# AmbaSat-1_version_2_0.net
KiCad netlist of a schematic drawn in EAGLE
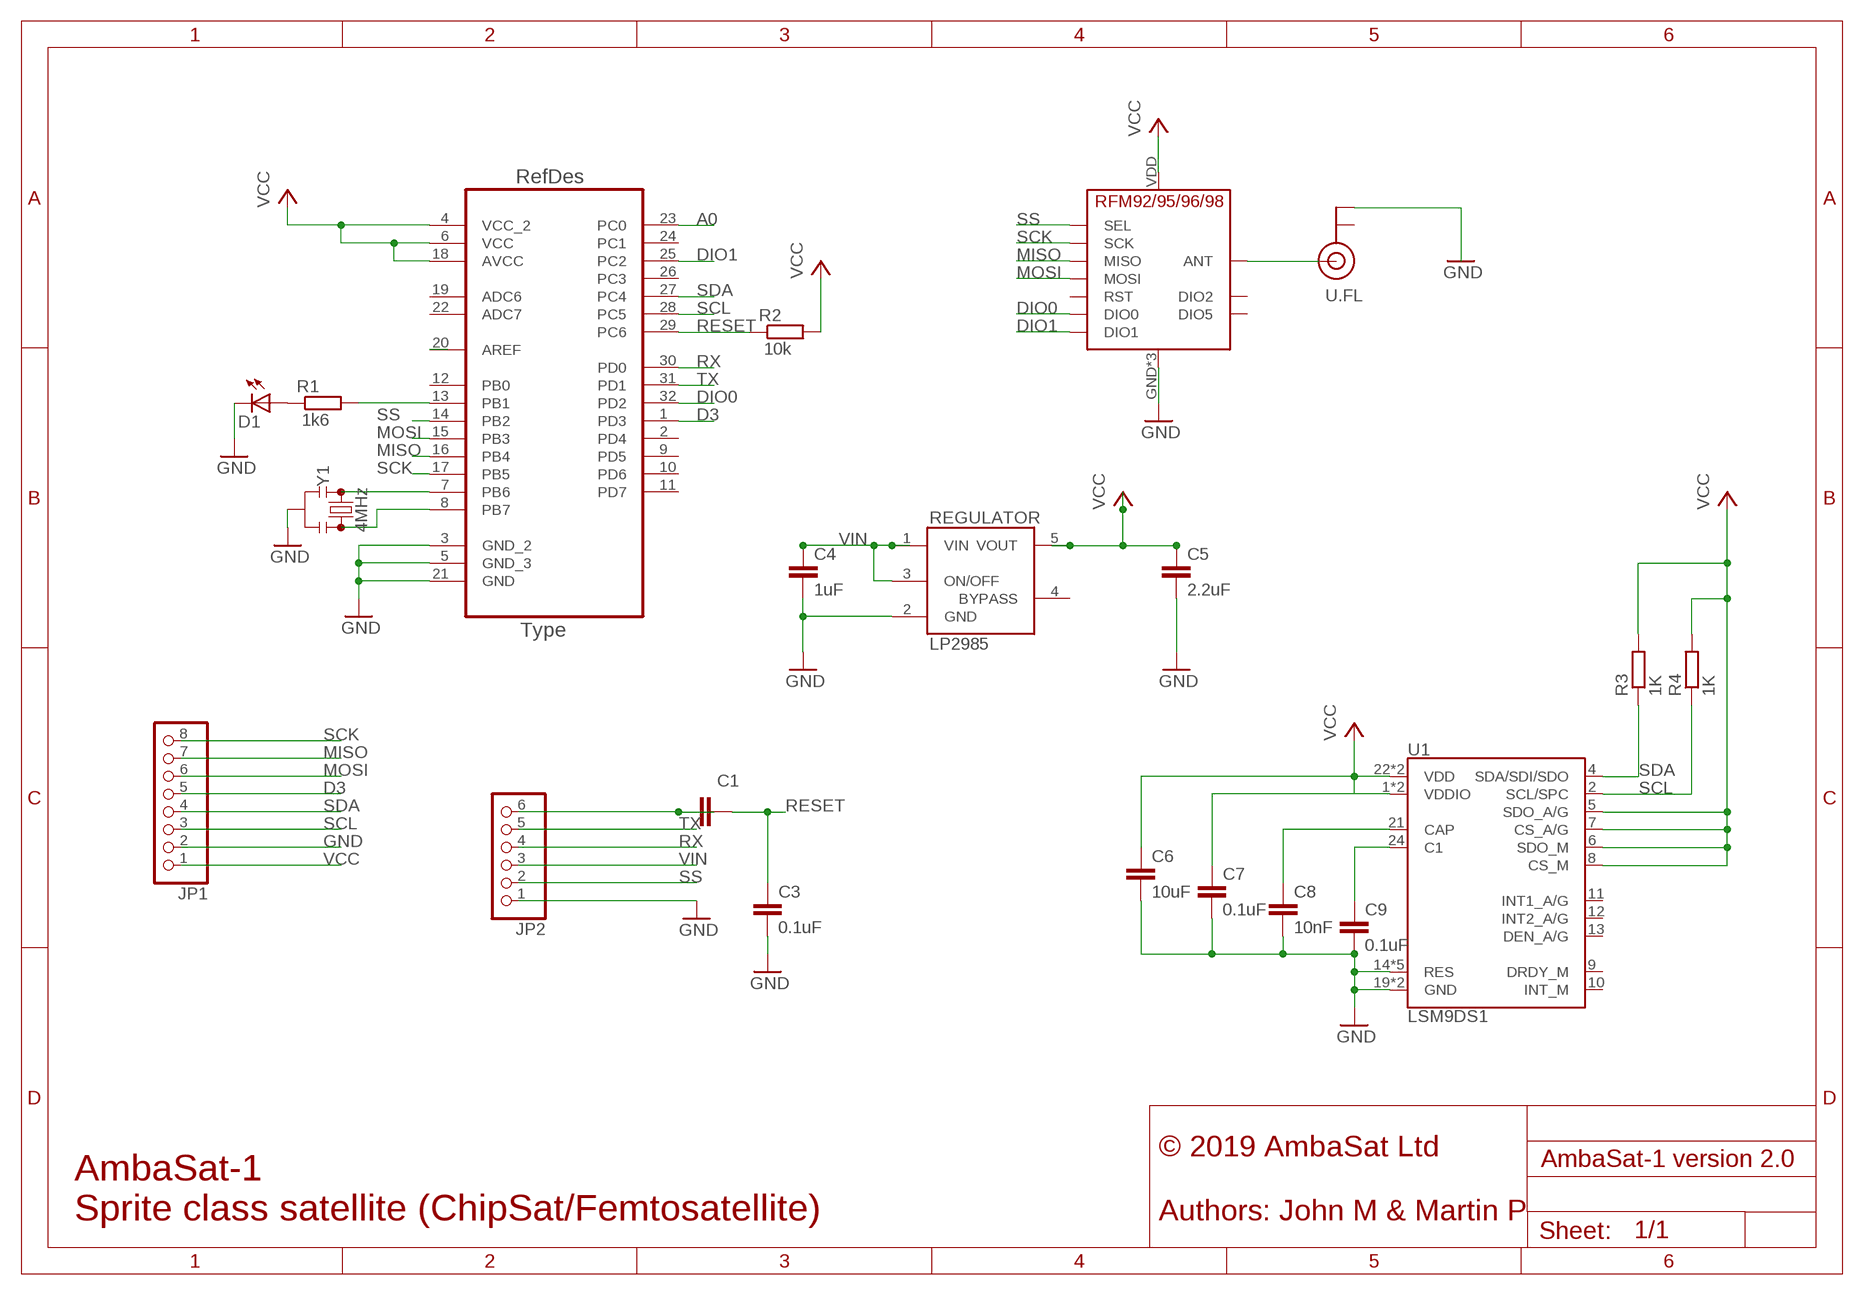
[diagram p0: schematic, sheet 1]

(export (version "E")
  (design (tool "Eeschema 10.0.6"))
  (components
    (comp (ref "ATMEGA328P-AU")
      (value "ATMEGA328P-AU")
      (footprint "eagle-import:QFP80P900X900X120-32N")
      (libsource (lib "eagle-import") (part "ATMEGA328P-AU"))
    )
    (comp (ref "C1")
      (value "1uF")
      (footprint "eagle-import:C0805K")
      (libsource (lib "eagle-import") (part "C-EUC0805K"))
    )
    (comp (ref "C3")
      (value "0.1uF")
      (footprint "eagle-import:C0805K")
      (libsource (lib "eagle-import") (part "C-EUC0805K"))
    )
    (comp (ref "C4")
      (value "1uF")
      (footprint "eagle-import:C0805K")
      (libsource (lib "eagle-import") (part "C-EUC0805K"))
    )
    (comp (ref "C5")
      (value "2.2uF")
      (footprint "eagle-import:C0805K")
      (libsource (lib "eagle-import") (part "C-EUC0805K"))
    )
    (comp (ref "C6")
      (value "10uF")
      (footprint "eagle-import:C0805K")
      (libsource (lib "eagle-import") (part "C-EUC0805K"))
    )
    (comp (ref "C7")
      (value "0.1uF")
      (footprint "eagle-import:C0805K")
      (libsource (lib "eagle-import") (part "C-EUC0805K"))
    )
    (comp (ref "C8")
      (value "10nF")
      (footprint "eagle-import:C0805K")
      (libsource (lib "eagle-import") (part "C-EUC0805K"))
    )
    (comp (ref "C9")
      (value "0.1uF")
      (footprint "eagle-import:C0805K")
      (libsource (lib "eagle-import") (part "C-EUC0805K"))
    )
    (comp (ref "D1")
      (value "LEDCHIP-LED0805")
      (footprint "eagle-import:CHIP-LED0805")
      (libsource (lib "eagle-import") (part "LEDCHIP-LED0805"))
    )
    (comp (ref "JP1")
      (value "PINHD-1X8")
      (footprint "eagle-import:1X08")
      (libsource (lib "eagle-import") (part "PINHD-1X8"))
    )
    (comp (ref "JP2")
      (value "PINHD-1X6")
      (footprint "eagle-import:1X06")
      (libsource (lib "eagle-import") (part "PINHD-1X6"))
    )
    (comp (ref "R1")
      (value "1k6")
      (footprint "eagle-import:M0805")
      (libsource (lib "eagle-import") (part "R-EU_M0805"))
    )
    (comp (ref "R2")
      (value "10k")
      (footprint "eagle-import:M0805")
      (libsource (lib "eagle-import") (part "R-EU_M0805"))
    )
    (comp (ref "R3")
      (value "1K")
      (footprint "eagle-import:M0805")
      (libsource (lib "eagle-import") (part "R-EU_M0805"))
    )
    (comp (ref "R4")
      (value "1K")
      (footprint "eagle-import:M0805")
      (libsource (lib "eagle-import") (part "R-EU_M0805"))
    )
    (comp (ref "REGULATOR")
      (value "LP2985AIM5-3.3")
      (footprint "eagle-import:SOT25")
      (libsource (lib "eagle-import") (part "LP2985AIM5-3.3"))
    )
    (comp (ref "RFM95")
      (value "RFM95")
      (footprint "eagle-import:RFM95")
      (libsource (lib "eagle-import") (part "RFM95"))
    )
    (comp (ref "U.FL")
      (value "U.FL")
      (footprint "eagle-import:U.FL")
      (libsource (lib "eagle-import") (part "U.FL"))
    )
    (comp (ref "U1")
      (value "LSM9DS1")
      (footprint "eagle-import:LGA24-8X4")
      (libsource (lib "eagle-import") (part "LSM9DS1"))
    )
    (comp (ref "Y1")
      (value "4MHz")
      (footprint "eagle-import:RESONATOR-SMD-4.5X2.0")
      (libsource (lib "eagle-import") (part "RESONATOR-4MHZSMD-4.5X2"))
    )
  )
  (nets
    (net (code "1") (name "/A0") (class "Default")
      (node (ref "ATMEGA328P-AU") (pin "23") (pinfunction "PC0_23") (pintype "bidirectional"))
    )
    (net (code "2") (name "/BYPASS") (class "Default")
      (node (ref "REGULATOR") (pin "4") (pinfunction "BYPASS_4") (pintype "power_in"))
    )
    (net (code "3") (name "/D3") (class "Default")
      (node (ref "ATMEGA328P-AU") (pin "1") (pinfunction "PD3_1") (pintype "bidirectional"))
      (node (ref "JP1") (pin "5") (pinfunction "5_5") (pintype "passive"))
    )
    (net (code "4") (name "/DIO0") (class "Default")
      (node (ref "ATMEGA328P-AU") (pin "32") (pinfunction "PD2_32") (pintype "bidirectional"))
      (node (ref "RFM95") (pin "DIO0") (pinfunction "DIO0_DIO0") (pintype "open_collector"))
    )
    (net (code "5") (name "/DIO1") (class "Default")
      (node (ref "ATMEGA328P-AU") (pin "25") (pinfunction "PC2_25") (pintype "bidirectional"))
      (node (ref "RFM95") (pin "DIO1") (pinfunction "DIO1_DIO1") (pintype "open_collector"))
    )
    (net (code "6") (name "/MISO") (class "Default")
      (node (ref "ATMEGA328P-AU") (pin "16") (pinfunction "PB4_16") (pintype "bidirectional"))
      (node (ref "JP1") (pin "7") (pinfunction "7_7") (pintype "passive"))
      (node (ref "RFM95") (pin "MISO") (pinfunction "MISO_MISO") (pintype "input"))
    )
    (net (code "7") (name "/MOSI") (class "Default")
      (node (ref "ATMEGA328P-AU") (pin "15") (pinfunction "PB3_15") (pintype "bidirectional"))
      (node (ref "JP1") (pin "6") (pinfunction "6_6") (pintype "passive"))
      (node (ref "RFM95") (pin "MOSI") (pinfunction "MOSI_MOSI") (pintype "output"))
    )
    (net (code "8") (name "/RESET") (class "Default")
      (node (ref "ATMEGA328P-AU") (pin "29") (pinfunction "PC6_29") (pintype "bidirectional"))
      (node (ref "C1") (pin "1") (pinfunction "1_1") (pintype "passive"))
      (node (ref "C3") (pin "1") (pinfunction "1_1") (pintype "passive"))
      (node (ref "R2") (pin "1") (pinfunction "1_1") (pintype "passive"))
    )
    (net (code "9") (name "/RX") (class "Default")
      (node (ref "ATMEGA328P-AU") (pin "30") (pinfunction "PD0_30") (pintype "bidirectional"))
      (node (ref "JP2") (pin "4") (pinfunction "4_4") (pintype "passive"))
    )
    (net (code "10") (name "/SCK") (class "Default")
      (node (ref "ATMEGA328P-AU") (pin "17") (pinfunction "PB5_17") (pintype "bidirectional"))
      (node (ref "JP1") (pin "8") (pinfunction "8_8") (pintype "passive"))
      (node (ref "RFM95") (pin "SCK") (pinfunction "SCK_SCK") (pintype "input"))
    )
    (net (code "11") (name "/SCL") (class "Default")
      (node (ref "ATMEGA328P-AU") (pin "28") (pinfunction "PC5_28") (pintype "bidirectional"))
      (node (ref "JP1") (pin "3") (pinfunction "3_3") (pintype "passive"))
      (node (ref "R4") (pin "1") (pinfunction "1_1") (pintype "passive"))
      (node (ref "U1") (pin "2") (pinfunction "SCL/SPC_2") (pintype "bidirectional"))
    )
    (net (code "12") (name "/SDA") (class "Default")
      (node (ref "ATMEGA328P-AU") (pin "27") (pinfunction "PC4_27") (pintype "bidirectional"))
      (node (ref "JP1") (pin "4") (pinfunction "4_4") (pintype "passive"))
      (node (ref "R3") (pin "1") (pinfunction "1_1") (pintype "passive"))
      (node (ref "U1") (pin "4") (pinfunction "SDA/SDI/SDO_4") (pintype "bidirectional"))
    )
    (net (code "13") (name "/SS") (class "Default")
      (node (ref "ATMEGA328P-AU") (pin "14") (pinfunction "PB2_14") (pintype "bidirectional"))
      (node (ref "JP2") (pin "2") (pinfunction "2_2") (pintype "passive"))
      (node (ref "RFM95") (pin "NSS") (pinfunction "SEL_NSS") (pintype "input"))
    )
    (net (code "14") (name "/TX") (class "Default")
      (node (ref "ATMEGA328P-AU") (pin "31") (pinfunction "PD1_31") (pintype "bidirectional"))
      (node (ref "JP2") (pin "5") (pinfunction "5_5") (pintype "passive"))
    )
    (net (code "15") (name "/VIN") (class "Default")
      (node (ref "C4") (pin "1") (pinfunction "1_1") (pintype "passive"))
      (node (ref "JP2") (pin "3") (pinfunction "3_3") (pintype "passive"))
      (node (ref "REGULATOR") (pin "1") (pinfunction "VIN_1") (pintype "power_in"))
      (node (ref "REGULATOR") (pin "3") (pinfunction "ON/OFF_3") (pintype "input"))
    )
    (net (code "16") (name "GND") (class "Default")
      (node (ref "ATMEGA328P-AU") (pin "21") (pinfunction "GND_21") (pintype "passive"))
      (node (ref "ATMEGA328P-AU") (pin "3") (pinfunction "GND_2_3") (pintype "passive"))
      (node (ref "ATMEGA328P-AU") (pin "5") (pinfunction "GND_3_5") (pintype "passive"))
      (node (ref "C3") (pin "2") (pinfunction "2_2") (pintype "passive"))
      (node (ref "C4") (pin "2") (pinfunction "2_2") (pintype "passive"))
      (node (ref "C5") (pin "2") (pinfunction "2_2") (pintype "passive"))
      (node (ref "C6") (pin "2") (pinfunction "2_2") (pintype "passive"))
      (node (ref "C7") (pin "2") (pinfunction "2_2") (pintype "passive"))
      (node (ref "C8") (pin "2") (pinfunction "2_2") (pintype "passive"))
      (node (ref "C9") (pin "2") (pinfunction "2_2") (pintype "passive"))
      (node (ref "D1") (pin "C") (pinfunction "C_C") (pintype "passive"))
      (node (ref "JP1") (pin "2") (pinfunction "2_2") (pintype "passive"))
      (node (ref "JP2") (pin "1") (pinfunction "1_1") (pintype "passive"))
      (node (ref "REGULATOR") (pin "2") (pinfunction "GND_2") (pintype "power_in"))
      (node (ref "RFM95") (pin "GND") (pinfunction "GND_GND") (pintype "power_in"))
      (node (ref "RFM95") (pin "GND1") (pinfunction "GND_GND1") (pintype "power_in"))
      (node (ref "RFM95") (pin "GND2") (pinfunction "GND_GND2") (pintype "power_in"))
      (node (ref "U1") (pin "14") (pinfunction "RES_14") (pintype "bidirectional"))
      (node (ref "U1") (pin "15") (pinfunction "RES_15") (pintype "bidirectional"))
      (node (ref "U1") (pin "16") (pinfunction "RES_16") (pintype "bidirectional"))
      (node (ref "U1") (pin "17") (pinfunction "RES_17") (pintype "bidirectional"))
      (node (ref "U1") (pin "18") (pinfunction "RES_18") (pintype "bidirectional"))
      (node (ref "U1") (pin "19") (pinfunction "GND_19") (pintype "bidirectional"))
      (node (ref "U1") (pin "20") (pinfunction "GND_20") (pintype "bidirectional"))
      (node (ref "Y1") (pin "2") (pinfunction "2_2") (pintype "passive"))
    )
    (net (code "17") (name "Net-(ATMEGA328P-AU-PB1)") (class "Default")
      (node (ref "ATMEGA328P-AU") (pin "13") (pinfunction "PB1_13") (pintype "bidirectional"))
      (node (ref "R1") (pin "2") (pinfunction "2_2") (pintype "passive"))
    )
    (net (code "18") (name "Net-(ATMEGA328P-AU-PB6)") (class "Default")
      (node (ref "ATMEGA328P-AU") (pin "7") (pinfunction "PB6_7") (pintype "bidirectional"))
      (node (ref "Y1") (pin "1") (pinfunction "1_1") (pintype "passive"))
    )
    (net (code "19") (name "Net-(ATMEGA328P-AU-PB7)") (class "Default")
      (node (ref "ATMEGA328P-AU") (pin "8") (pinfunction "PB7_8") (pintype "bidirectional"))
      (node (ref "Y1") (pin "3") (pinfunction "3_3") (pintype "passive"))
    )
    (net (code "20") (name "Net-(C1-Pad2)") (class "Default")
      (node (ref "C1") (pin "2") (pinfunction "2_2") (pintype "passive"))
      (node (ref "JP2") (pin "6") (pinfunction "6_6") (pintype "passive"))
    )
    (net (code "21") (name "Net-(D1-PadA)") (class "Default")
      (node (ref "D1") (pin "A") (pinfunction "A_A") (pintype "passive"))
      (node (ref "R1") (pin "1") (pinfunction "1_1") (pintype "passive"))
    )
    (net (code "22") (name "Net-(U1-C1)") (class "Default")
      (node (ref "C9") (pin "1") (pinfunction "1_1") (pintype "passive"))
      (node (ref "U1") (pin "24") (pinfunction "C1_24") (pintype "bidirectional"))
    )
    (net (code "23") (name "Net-(U1-CAP)") (class "Default")
      (node (ref "C8") (pin "1") (pinfunction "1_1") (pintype "passive"))
      (node (ref "U1") (pin "21") (pinfunction "CAP_21") (pintype "bidirectional"))
    )
    (net (code "24") (name "VCC") (class "Default")
      (node (ref "ATMEGA328P-AU") (pin "18") (pinfunction "AVCC_18") (pintype "power_in"))
      (node (ref "ATMEGA328P-AU") (pin "4") (pinfunction "VCC_2_4") (pintype "power_in"))
      (node (ref "ATMEGA328P-AU") (pin "6") (pinfunction "VCC_6") (pintype "power_in"))
      (node (ref "C5") (pin "1") (pinfunction "1_1") (pintype "passive"))
      (node (ref "C6") (pin "1") (pinfunction "1_1") (pintype "passive"))
      (node (ref "C7") (pin "1") (pinfunction "1_1") (pintype "passive"))
      (node (ref "JP1") (pin "1") (pinfunction "1_1") (pintype "passive"))
      (node (ref "R2") (pin "2") (pinfunction "2_2") (pintype "passive"))
      (node (ref "R3") (pin "2") (pinfunction "2_2") (pintype "passive"))
      (node (ref "R4") (pin "2") (pinfunction "2_2") (pintype "passive"))
      (node (ref "REGULATOR") (pin "5") (pinfunction "VOUT_5") (pintype "power_in"))
      (node (ref "RFM95") (pin "VDD") (pinfunction "VCC_VDD") (pintype "power_in"))
      (node (ref "U1") (pin "1") (pinfunction "VDDIO_1") (pintype "bidirectional"))
      (node (ref "U1") (pin "22") (pinfunction "VDD_22") (pintype "bidirectional"))
      (node (ref "U1") (pin "23") (pinfunction "VDD_23") (pintype "bidirectional"))
      (node (ref "U1") (pin "3") (pinfunction "VDDIO_3") (pintype "bidirectional"))
      (node (ref "U1") (pin "5") (pinfunction "SDO_A/G_5") (pintype "bidirectional"))
      (node (ref "U1") (pin "6") (pinfunction "SDO_M_6") (pintype "bidirectional"))
      (node (ref "U1") (pin "7") (pinfunction "CS_A/G_7") (pintype "bidirectional"))
      (node (ref "U1") (pin "8") (pinfunction "CS_M_8") (pintype "bidirectional"))
    )
    (net (code "25") (name "unconnected-(ATMEGA328P-AU-ADC6-Pad19)") (class "Default")
      (node (ref "ATMEGA328P-AU") (pin "19") (pinfunction "ADC6_19") (pintype "input"))
    )
    (net (code "26") (name "unconnected-(ATMEGA328P-AU-ADC7-Pad22)") (class "Default")
      (node (ref "ATMEGA328P-AU") (pin "22") (pinfunction "ADC7_22") (pintype "input"))
    )
    (net (code "27") (name "unconnected-(ATMEGA328P-AU-AREF-Pad20)") (class "Default")
      (node (ref "ATMEGA328P-AU") (pin "20") (pinfunction "AREF_20") (pintype "input"))
    )
    (net (code "28") (name "unconnected-(ATMEGA328P-AU-PB0-Pad12)") (class "Default")
      (node (ref "ATMEGA328P-AU") (pin "12") (pinfunction "PB0_12") (pintype "bidirectional"))
    )
    (net (code "29") (name "unconnected-(ATMEGA328P-AU-PC1-Pad24)") (class "Default")
      (node (ref "ATMEGA328P-AU") (pin "24") (pinfunction "PC1_24") (pintype "bidirectional"))
    )
    (net (code "30") (name "unconnected-(ATMEGA328P-AU-PC3-Pad26)") (class "Default")
      (node (ref "ATMEGA328P-AU") (pin "26") (pinfunction "PC3_26") (pintype "bidirectional"))
    )
    (net (code "31") (name "unconnected-(ATMEGA328P-AU-PD4-Pad2)") (class "Default")
      (node (ref "ATMEGA328P-AU") (pin "2") (pinfunction "PD4_2") (pintype "bidirectional"))
    )
    (net (code "32") (name "unconnected-(ATMEGA328P-AU-PD5-Pad9)") (class "Default")
      (node (ref "ATMEGA328P-AU") (pin "9") (pinfunction "PD5_9") (pintype "bidirectional"))
    )
    (net (code "33") (name "unconnected-(ATMEGA328P-AU-PD6-Pad10)") (class "Default")
      (node (ref "ATMEGA328P-AU") (pin "10") (pinfunction "PD6_10") (pintype "bidirectional"))
    )
    (net (code "34") (name "unconnected-(ATMEGA328P-AU-PD7-Pad11)") (class "Default")
      (node (ref "ATMEGA328P-AU") (pin "11") (pinfunction "PD7_11") (pintype "bidirectional"))
    )
    (net (code "35") (name "unconnected-(RFM95-PadANT)") (class "Default")
      (node (ref "RFM95") (pin "ANT") (pinfunction "ANT_ANT") (pintype "passive"))
    )
    (net (code "36") (name "unconnected-(RFM95-PadDIO2)") (class "Default")
      (node (ref "RFM95") (pin "DIO2") (pinfunction "DIO2_DIO2") (pintype "open_collector"))
    )
    (net (code "37") (name "unconnected-(RFM95-PadDIO5)") (class "Default")
      (node (ref "RFM95") (pin "DIO5") (pinfunction "DIO5_DIO5") (pintype "open_collector"))
    )
    (net (code "38") (name "unconnected-(RFM95-PadRST)") (class "Default")
      (node (ref "RFM95") (pin "RST") (pinfunction "RST_RST") (pintype "open_collector"))
    )
    (net (code "39") (name "unconnected-(U.FL-GND-Pad1)") (class "Default")
      (node (ref "U.FL") (pin "1") (pinfunction "GND_1") (pintype "bidirectional"))
    )
    (net (code "40") (name "unconnected-(U.FL-GND-Pad2)") (class "Default")
      (node (ref "U.FL") (pin "2") (pinfunction "GND_2") (pintype "bidirectional"))
    )
    (net (code "41") (name "unconnected-(U.FL-SIGNAL-PadFEED)") (class "Default")
      (node (ref "U.FL") (pin "FEED") (pinfunction "SIGNAL_FEED") (pintype "bidirectional"))
    )
    (net (code "42") (name "unconnected-(U1-DEN_A{slash}G-Pad13)") (class "Default")
      (node (ref "U1") (pin "13") (pinfunction "DEN_A/G_13") (pintype "bidirectional"))
    )
    (net (code "43") (name "unconnected-(U1-DRDY_M-Pad9)") (class "Default")
      (node (ref "U1") (pin "9") (pinfunction "DRDY_M_9") (pintype "bidirectional"))
    )
    (net (code "44") (name "unconnected-(U1-INT1_A{slash}G-Pad11)") (class "Default")
      (node (ref "U1") (pin "11") (pinfunction "INT1_A/G_11") (pintype "bidirectional"))
    )
    (net (code "45") (name "unconnected-(U1-INT2_A{slash}G-Pad12)") (class "Default")
      (node (ref "U1") (pin "12") (pinfunction "INT2_A/G_12") (pintype "bidirectional"))
    )
    (net (code "46") (name "unconnected-(U1-INT_M-Pad10)") (class "Default")
      (node (ref "U1") (pin "10") (pinfunction "INT_M_10") (pintype "bidirectional"))
    )
  )
)
